# Tiny817_Xplained_Pro_current_measurement.net
KiCad netlist of a schematic drawn in Altium Designer
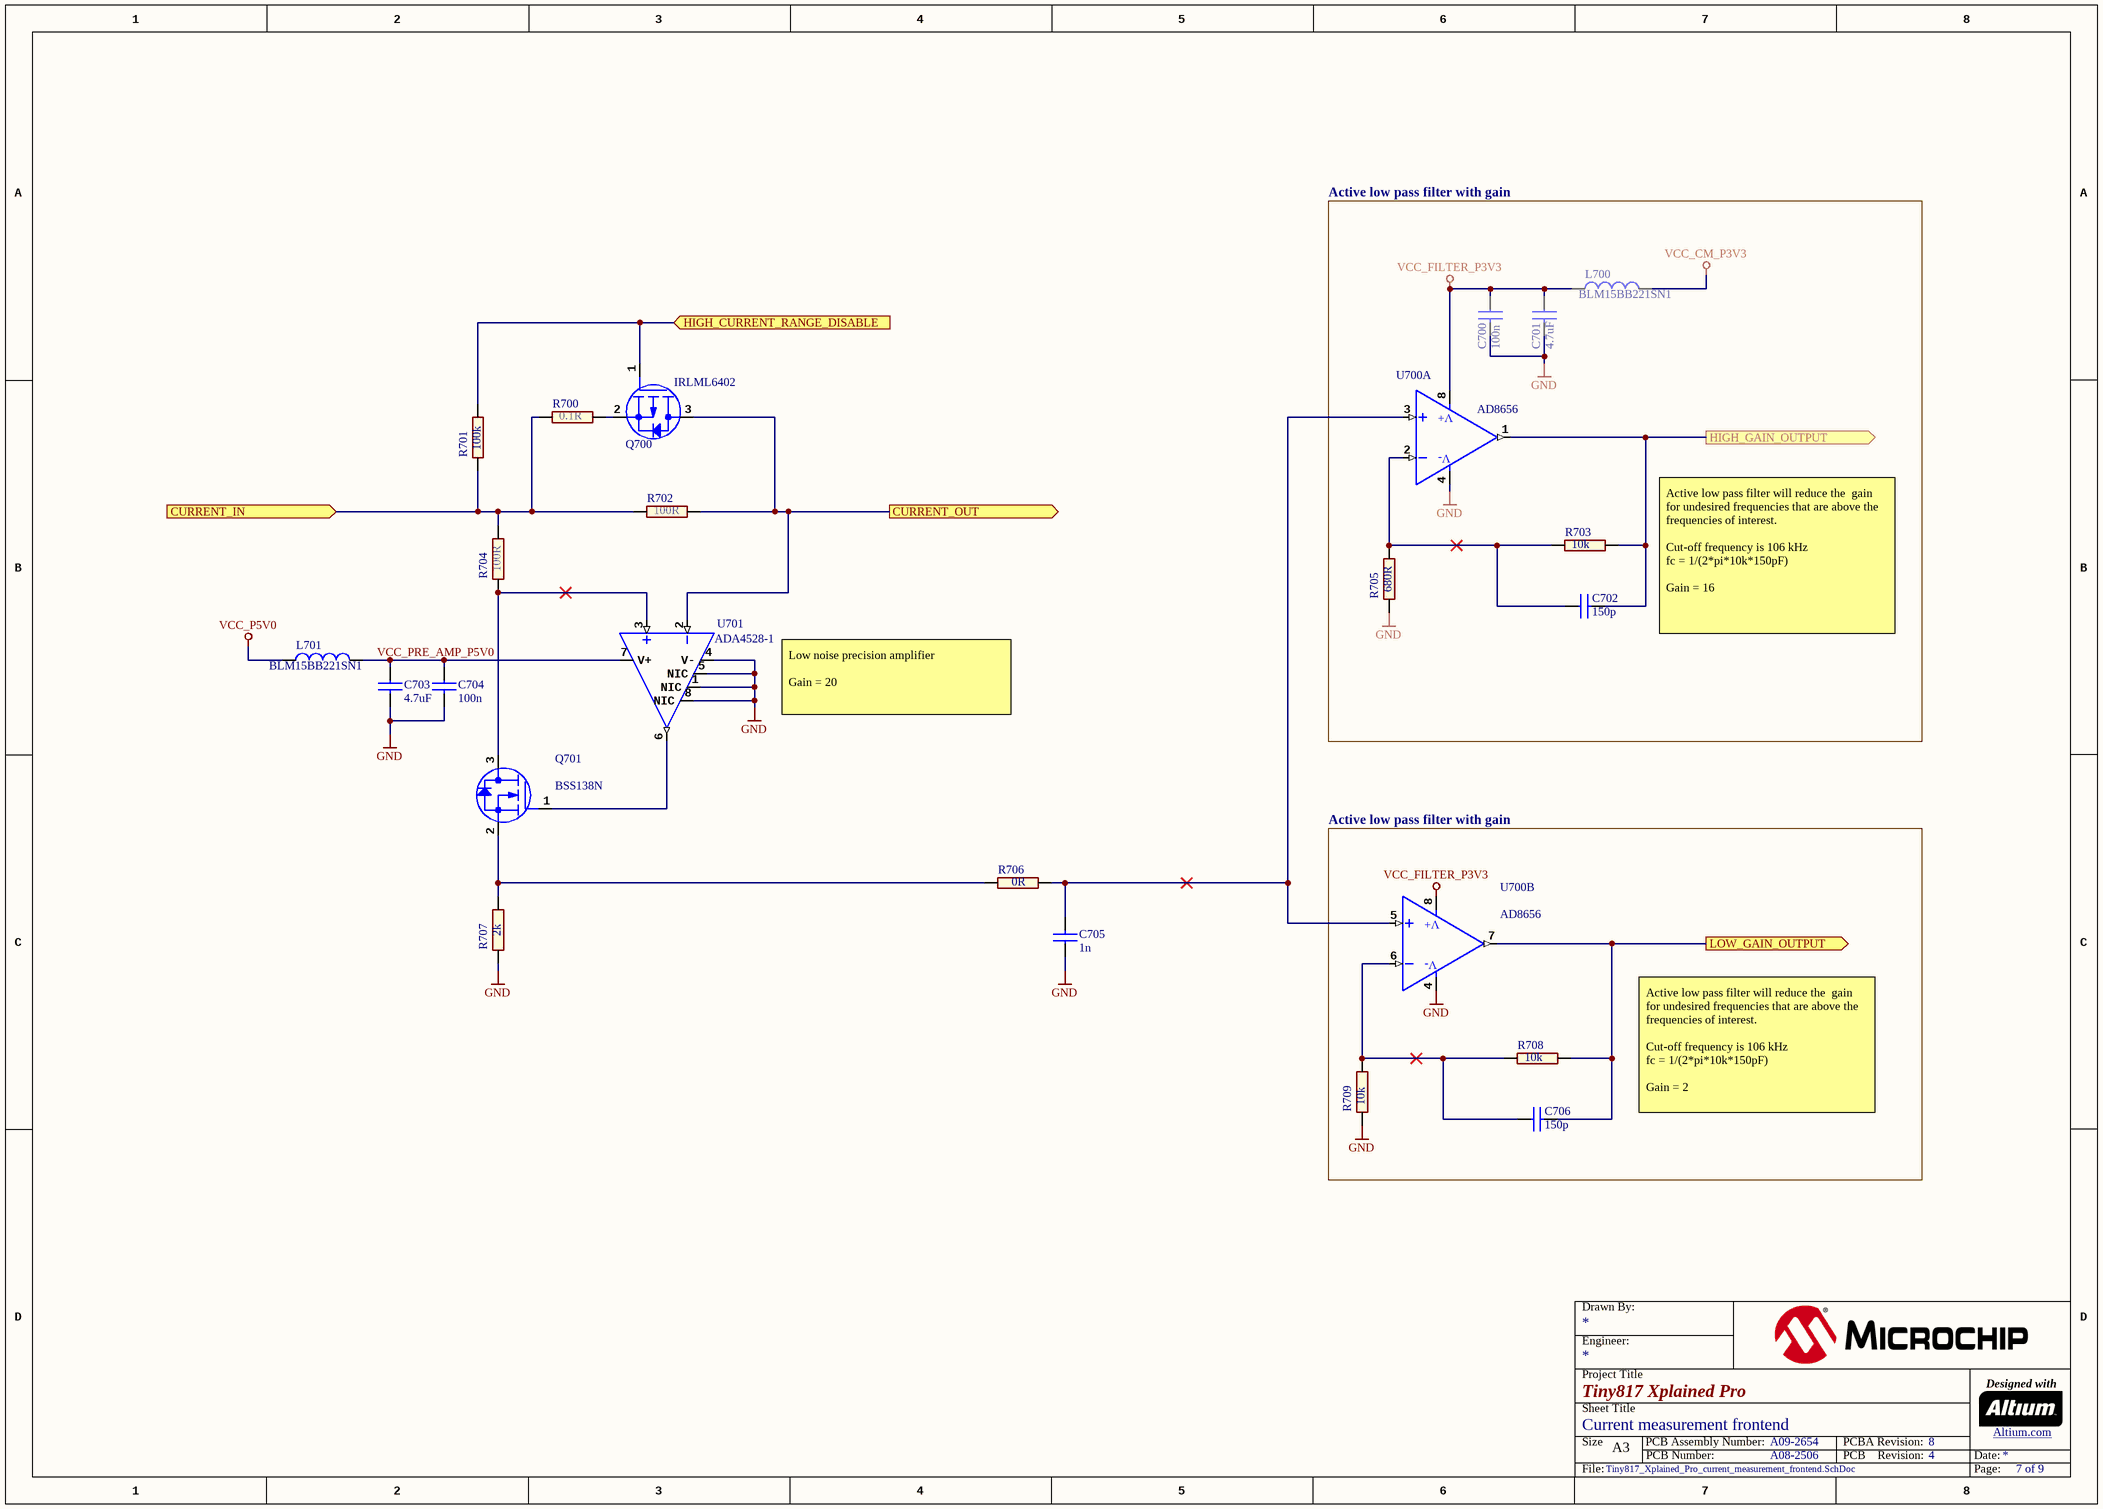
[diagram p0: Tiny817_Xplained_Pro_current_measurement_frontend.SchDoc]

(export (version "E")
  (design (tool "Eeschema 10.0.6"))
  (components
    (comp (ref "C700")
      (value "100n")
      (footprint "AP1-00053")
      (description "Ceramic capacitor, SMD 0402, X7R, 16V, +/-10%")
      (fields (field (name "TOLERANCE") "16V, +/-10%") (field (name "MANUFACTURER") "Kemet"))
      (libsource (lib "AltiumDbLib") (part "CAP-NONPOL"))
    )
    (comp (ref "C701")
      (value "4.7uF")
      (footprint "AP1-00117")
      (description "Ceramic capacitor, SMD 0603, X5R, 10V, 10% (de31036)")
      (fields (field (name "TOLERANCE") "10%") (field (name "MANUFACTURER") "WALSIN Technology Corporation"))
      (libsource (lib "AltiumDbLib") (part "CAP-NONPOL"))
    )
    (comp (ref "C702")
      (value "150p")
      (footprint "AP1-00053")
      (description "Ceramic capacitor, SMD 0402, X7R, 50V, +/-10%")
      (fields (field (name "TOLERANCE") "50V, +/-10%") (field (name "MANUFACTURER") "Yageo"))
      (libsource (lib "AltiumDbLib") (part "CAP-NONPOL"))
    )
    (comp (ref "C703")
      (value "4.7uF")
      (footprint "AP1-00117")
      (description "Ceramic capacitor, SMD 0603, X5R, 10V, 10% (de31036)")
      (fields (field (name "TOLERANCE") "10%") (field (name "MANUFACTURER") "WALSIN Technology Corporation"))
      (libsource (lib "AltiumDbLib") (part "CAP-NONPOL"))
    )
    (comp (ref "C704")
      (value "100n")
      (footprint "AP1-00053")
      (description "Ceramic capacitor, SMD 0402, X7R, 16V, +/-10%")
      (fields (field (name "TOLERANCE") "16V, +/-10%") (field (name "MANUFACTURER") "Kemet"))
      (libsource (lib "AltiumDbLib") (part "CAP-NONPOL"))
    )
    (comp (ref "C705")
      (value "1n")
      (footprint "AP1-00053")
      (description "Ceramic capacitor, SMD 0402, X7R, 50V, +/-10%")
      (fields (field (name "TOLERANCE") "50V, +/-10%") (field (name "MANUFACTURER") "Yageo"))
      (libsource (lib "AltiumDbLib") (part "CAP-NONPOL"))
    )
    (comp (ref "C706")
      (value "150p")
      (footprint "AP1-00053")
      (description "Ceramic capacitor, SMD 0402, X7R, 50V, +/-10%")
      (fields (field (name "TOLERANCE") "50V, +/-10%") (field (name "MANUFACTURER") "Yageo"))
      (libsource (lib "AltiumDbLib") (part "CAP-NONPOL"))
    )
    (comp (ref "L700")
      (value "BLM15BB221SN1")
      (footprint "AP3-00028")
      (description "SMD RF inductor 0402. Z=220Ohm (@100MHz), Max R(dc)=0.80Ohm, Max current=200mA")
      (fields (field (name "TOLERANCE") "±25%") (field (name "MANUFACTURER") "Murata"))
      (libsource (lib "") (part "INDUCTOR_1"))
    )
    (comp (ref "L701")
      (value "BLM15BB221SN1")
      (footprint "AP3-00028")
      (description "SMD RF inductor 0402. Z=220Ohm (@100MHz), Max R(dc)=0.80Ohm, Max current=200mA")
      (fields (field (name "TOLERANCE") "±25%") (field (name "MANUFACTURER") "Murata"))
      (libsource (lib "AltiumDbLib") (part "INDUCTOR"))
    )
    (comp (ref "Q700")
      (value "IRLML6402")
      (footprint "AP5-00002")
      (description "P-ch. MOSFET. -30V, -3.7A continuous,RDS(ON)=0.05Ohm@VGS=-4,5V, RDS(ON)=0.08Ohm@VGS=-2.5V")
      (fields (field (name "MANUFACTURER") "International Rectifier") (field (name "MPN") "IRLML6402PBF"))
      (libsource (lib "AltiumDbLib") (part "MOSFET_P_GSD"))
    )
    (comp (ref "Q701")
      (value "BSS138N")
      (footprint "AP5-00002")
      (fields (field (name "MANUFACTURER") "Infineon"))
      (libsource (lib "AltiumDbLib") (part "MOSFET_N_GSD"))
    )
    (comp (ref "R700")
      (value "0.1R")
      (footprint "AP2-00076")
      (description "WSL0603R1000FEA, metal strip resistor, 0.1 Ohm, +-1%, 0603 SMD, 1/10 W, TEMPCO +-75 ppm/Â°C")
      (fields (field (name "MANUFACTURER") "Vishay") (field (name "MPN") "WSL0603R1000FEA"))
      (libsource (lib "AltiumDbLib") (part "R2"))
    )
    (comp (ref "R701")
      (value "100k")
      (footprint "AP2-00011")
      (description "Thick film resistor, SMD 0402, 1/16W, 1%")
      (fields (field (name "TOLERANCE") "1 %") (field (name "MANUFACTURER") "ASJ Holdings"))
      (libsource (lib "") (part "R2_1"))
    )
    (comp (ref "R702")
      (value "100R")
      (footprint "AP2-00076")
      (description "ERA-3YEB101V, metal film, 100R Â±0.1%, resistor in 0603 at 100mW, TEMPCO Â±25ppm/Â°C, Max V=75V")
      (fields (field (name "MANUFACTURER") "Panasonic") (field (name "MPN") "ERA3YEB101V"))
      (libsource (lib "AltiumDbLib") (part "R2"))
    )
    (comp (ref "R703")
      (value "10k")
      (footprint "AP2-00011")
      (description "Thick film resistor, SMD 0402, 1/16W, 1%")
      (fields (field (name "TOLERANCE") "1 %") (field (name "MANUFACTURER") "Vishay"))
      (libsource (lib "AltiumDbLib") (part "R2"))
    )
    (comp (ref "R704")
      (value "100R")
      (footprint "AP2-00076")
      (description "ERA-3YEB101V, metal film, 100R Â±0.1%, resistor in 0603 at 100mW, TEMPCO Â±25ppm/Â°C, Max V=75V")
      (fields (field (name "MANUFACTURER") "Panasonic") (field (name "MPN") "ERA3YEB101V"))
      (libsource (lib "") (part "R2_1"))
    )
    (comp (ref "R705")
      (value "680R")
      (footprint "AP2-00011")
      (description "Thick film resistor, SMD 0402, 1/16W, 1%")
      (fields (field (name "TOLERANCE") "1 %") (field (name "MANUFACTURER") "ASJ Holdings"))
      (libsource (lib "") (part "R2_1"))
    )
    (comp (ref "R706")
      (value "0R")
      (footprint "AP2-00011")
      (description "RES 0.0 OHM 1/16W 0402 SMD")
      (fields (field (name "TOLERANCE") "1 %") (field (name "MANUFACTURER") "(n/a)"))
      (libsource (lib "") (part "R2_2"))
    )
    (comp (ref "R707")
      (value "2k")
      (footprint "AP2-00076")
      (description "Thick film resistor, SMD 0603, 1/10W, 1%")
      (fields (field (name "TOLERANCE") "1 %") (field (name "MANUFACTURER") "Yageo"))
      (libsource (lib "") (part "R2_1"))
    )
    (comp (ref "R708")
      (value "10k")
      (footprint "AP2-00011")
      (description "Thick film resistor, SMD 0402, 1/16W, 1%")
      (fields (field (name "TOLERANCE") "1 %") (field (name "MANUFACTURER") "Vishay"))
      (libsource (lib "AltiumDbLib") (part "R2"))
    )
    (comp (ref "R709")
      (value "10k")
      (footprint "AP2-00011")
      (description "Thick film resistor, SMD 0402, 1/16W, 1%")
      (fields (field (name "TOLERANCE") "1 %") (field (name "MANUFACTURER") "Vishay"))
      (libsource (lib "") (part "R2_1"))
    )
    (comp (ref "U700")
      (value "AD8656")
      (footprint "AP6-00100")
      (description "AD8656, dual low noise precision OpAmp, rail-to-rail, low offset 250uV, GBP 28 MHz, 8MSOP")
      (fields (field (name "MANUFACTURER") "Analog Devices") (field (name "MPN") "AD8656ARMZ"))
      (libsource (lib "AltiumDbLib") (part "AD8656"))
    )
    (comp (ref "U701")
      (value "ADA4528-1")
      (footprint "AP6-00100")
      (fields (field (name "MANUFACTURER") "Analog Devices") (field (name "MPN") "ADA4528-1ARMZ"))
      (libsource (lib "AltiumDbLib") (part "ADA4528-1"))
    )
  )
  (nets
    (net (code "1") (name "/CURRENT_IN") (class "Default")
      (node (ref "R700") (pin "1") (pinfunction "1_1") (pintype "passive"))
      (node (ref "R701") (pin "1") (pinfunction "1_1") (pintype "passive"))
      (node (ref "R702") (pin "1") (pinfunction "1_1") (pintype "passive"))
      (node (ref "R704") (pin "2") (pinfunction "2_2") (pintype "passive"))
    )
    (net (code "2") (name "/CURRENT_OUT") (class "Default")
      (node (ref "Q700") (pin "3") (pinfunction "D_3") (pintype "passive"))
      (node (ref "R702") (pin "2") (pinfunction "2_2") (pintype "passive"))
      (node (ref "U701") (pin "2") (pinfunction "IN-_2") (pintype "input"))
    )
    (net (code "3") (name "/HIGH_CURRENT_RANGE_DISABLE") (class "Default")
      (node (ref "Q700") (pin "1") (pinfunction "G_1") (pintype "passive"))
      (node (ref "R701") (pin "2") (pinfunction "2_2") (pintype "passive"))
    )
    (net (code "4") (name "/HIGH_GAIN_OUTPUT") (class "Default")
      (node (ref "C702") (pin "2") (pinfunction "2_2") (pintype "passive"))
      (node (ref "R703") (pin "2") (pinfunction "2_2") (pintype "passive"))
      (node (ref "U700") (pin "1") (pinfunction "OUTA_1") (pintype "output"))
    )
    (net (code "5") (name "/LOW_GAIN_OUTPUT") (class "Default")
      (node (ref "C706") (pin "2") (pinfunction "2_2") (pintype "passive"))
      (node (ref "R708") (pin "2") (pinfunction "2_2") (pintype "passive"))
      (node (ref "U700") (pin "7") (pinfunction "OUTB_7") (pintype "output"))
    )
    (net (code "6") (name "/VCC_PRE_AMP_P5V0") (class "Default")
      (node (ref "C703") (pin "1") (pinfunction "1_1") (pintype "passive"))
      (node (ref "C704") (pin "1") (pinfunction "1_1") (pintype "passive"))
      (node (ref "L701") (pin "2") (pinfunction "2_2") (pintype "passive"))
      (node (ref "U701") (pin "7") (pinfunction "V+_7") (pintype "power_in"))
    )
    (net (code "7") (name "GND") (class "Default")
      (node (ref "C700") (pin "2") (pinfunction "2_2") (pintype "passive"))
      (node (ref "C701") (pin "2") (pinfunction "2_2") (pintype "passive"))
      (node (ref "C703") (pin "2") (pinfunction "2_2") (pintype "passive"))
      (node (ref "C704") (pin "2") (pinfunction "2_2") (pintype "passive"))
      (node (ref "C705") (pin "1") (pinfunction "1_1") (pintype "passive"))
      (node (ref "R705") (pin "1") (pinfunction "1_1") (pintype "passive"))
      (node (ref "R707") (pin "1") (pinfunction "1_1") (pintype "passive"))
      (node (ref "R709") (pin "1") (pinfunction "1_1") (pintype "passive"))
      (node (ref "U700") (pin "4") (pinfunction "V-_4") (pintype "power_in"))
      (node (ref "U701") (pin "1") (pinfunction "NIC_1") (pintype "passive"))
      (node (ref "U701") (pin "4") (pinfunction "V-_4") (pintype "power_in"))
      (node (ref "U701") (pin "5") (pinfunction "NIC_5") (pintype "passive"))
      (node (ref "U701") (pin "8") (pinfunction "NIC_8") (pintype "passive"))
    )
    (net (code "8") (name "Net-(Q700-S)") (class "Default")
      (node (ref "Q700") (pin "2") (pinfunction "S_2") (pintype "passive"))
      (node (ref "R700") (pin "2") (pinfunction "2_2") (pintype "passive"))
    )
    (net (code "9") (name "Net-(Q701-D)") (class "Default")
      (node (ref "Q701") (pin "3") (pinfunction "D_3") (pintype "passive"))
      (node (ref "R704") (pin "1") (pinfunction "1_1") (pintype "passive"))
      (node (ref "U701") (pin "3") (pinfunction "IN+_3") (pintype "input"))
    )
    (net (code "10") (name "Net-(Q701-G)") (class "Default")
      (node (ref "Q701") (pin "1") (pinfunction "G_1") (pintype "passive"))
      (node (ref "U701") (pin "6") (pinfunction "OUT_6") (pintype "output"))
    )
    (net (code "11") (name "Net-(Q701-S)") (class "Default")
      (node (ref "Q701") (pin "2") (pinfunction "S_2") (pintype "passive"))
      (node (ref "R706") (pin "2") (pinfunction "2_2") (pintype "passive"))
      (node (ref "R707") (pin "2") (pinfunction "2_2") (pintype "passive"))
    )
    (net (code "12") (name "Net-(U700A-INA_+)") (class "Default")
      (node (ref "C705") (pin "2") (pinfunction "2_2") (pintype "passive"))
      (node (ref "R706") (pin "1") (pinfunction "1_1") (pintype "passive"))
      (node (ref "U700") (pin "3") (pinfunction "INA_+_3") (pintype "input"))
      (node (ref "U700") (pin "5") (pinfunction "INB_+_5") (pintype "input"))
    )
    (net (code "13") (name "Net-(U700A-INA_-)") (class "Default")
      (node (ref "C702") (pin "1") (pinfunction "1_1") (pintype "passive"))
      (node (ref "R703") (pin "1") (pinfunction "1_1") (pintype "passive"))
      (node (ref "R705") (pin "2") (pinfunction "2_2") (pintype "passive"))
      (node (ref "U700") (pin "2") (pinfunction "INA_-_2") (pintype "input"))
    )
    (net (code "14") (name "Net-(U700B-INB_-)") (class "Default")
      (node (ref "C706") (pin "1") (pinfunction "1_1") (pintype "passive"))
      (node (ref "R708") (pin "1") (pinfunction "1_1") (pintype "passive"))
      (node (ref "R709") (pin "2") (pinfunction "2_2") (pintype "passive"))
      (node (ref "U700") (pin "6") (pinfunction "INB_-_6") (pintype "input"))
    )
    (net (code "15") (name "VCC_CM_P3V3") (class "Default")
      (node (ref "L700") (pin "1") (pinfunction "1_1") (pintype "passive"))
    )
    (net (code "16") (name "VCC_FILTER_P3V3") (class "Default")
      (node (ref "C700") (pin "1") (pinfunction "1_1") (pintype "passive"))
      (node (ref "C701") (pin "1") (pinfunction "1_1") (pintype "passive"))
      (node (ref "L700") (pin "2") (pinfunction "2_2") (pintype "passive"))
      (node (ref "U700") (pin "8") (pinfunction "V+_8") (pintype "power_in"))
    )
    (net (code "17") (name "VCC_P5V0") (class "Default")
      (node (ref "L701") (pin "1") (pinfunction "1_1") (pintype "passive"))
    )
  )
)
